# NixieClock_2_1.net
KiCad netlist of a schematic drawn in EAGLE
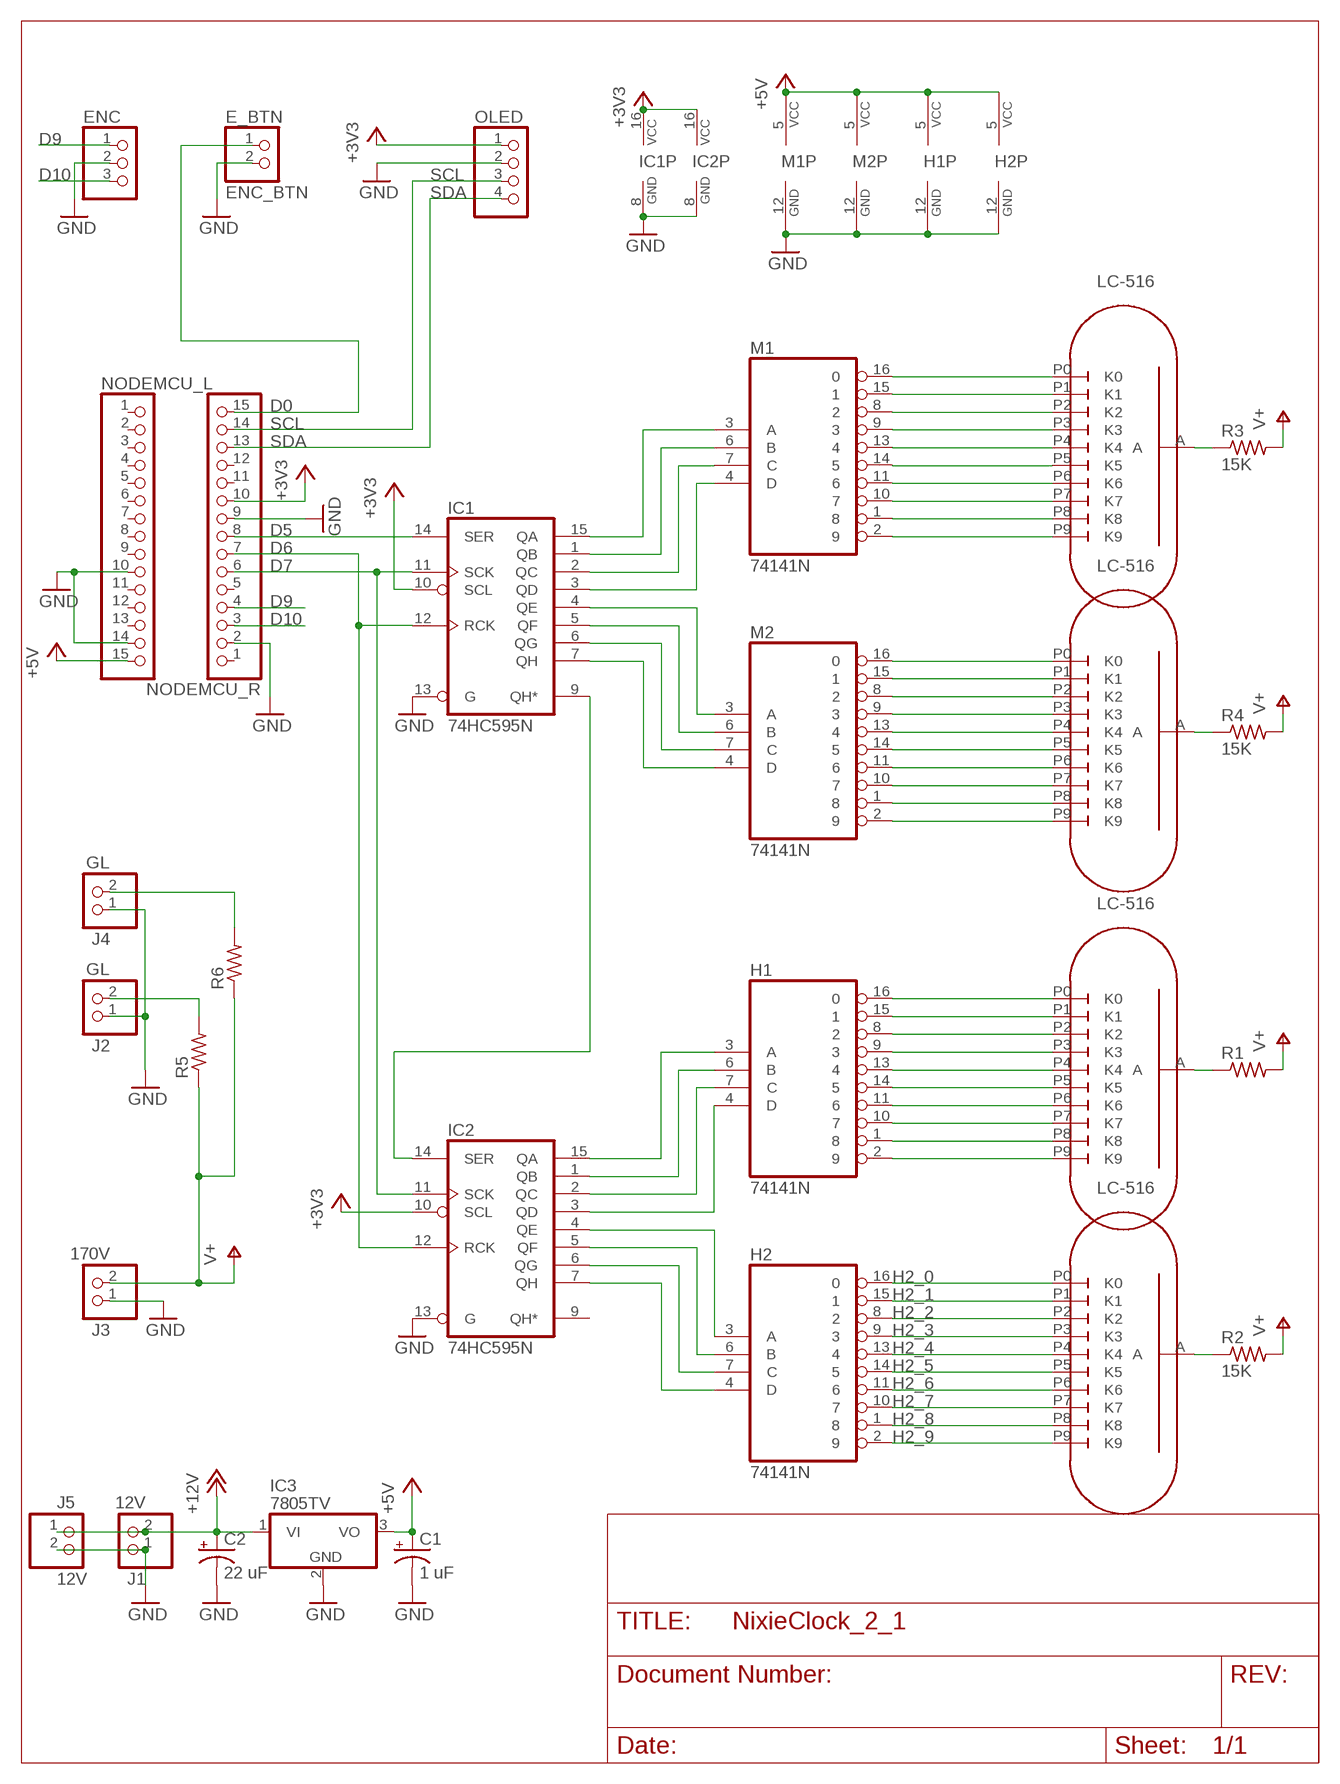
[diagram p0: schematic, sheet 1]

(export (version "E")
  (design (tool "Eeschema 10.0.6"))
  (components
    (comp (ref "C1")
      (value "1 uF")
      (footprint "eagle-import:TT2D5")
      (libsource (lib "eagle-import") (part "CPOL-USTT2D5"))
    )
    (comp (ref "C2")
      (value "22 uF")
      (footprint "eagle-import:TT2D5")
      (libsource (lib "eagle-import") (part "CPOL-USTT2D5"))
    )
    (comp (ref "ENC")
      (value "PINHD-1X3")
      (footprint "eagle-import:1X03")
      (libsource (lib "eagle-import") (part "PINHD-1X3"))
    )
    (comp (ref "E_BTN")
      (value "ENC_BTN")
      (footprint "eagle-import:1X02")
      (libsource (lib "eagle-import") (part "PINHD-1X2"))
    )
    (comp (ref "H1")
      (value "74141N")
      (footprint "eagle-import:DIL16")
      (libsource (lib "eagle-import") (part "74141N"))
    )
    (comp (ref "H2")
      (value "74141N")
      (footprint "eagle-import:DIL16")
      (libsource (lib "eagle-import") (part "74141N"))
    )
    (comp (ref "IC1")
      (value "74HC595N")
      (footprint "eagle-import:DIL16")
      (libsource (lib "eagle-import") (part "74595NHC"))
    )
    (comp (ref "IC2")
      (value "74HC595N")
      (footprint "eagle-import:DIL16")
      (libsource (lib "eagle-import") (part "74595NHC"))
    )
    (comp (ref "IC3")
      (value "7805TV")
      (footprint "eagle-import:TO220V")
      (libsource (lib "eagle-import") (part "78TV05"))
    )
    (comp (ref "J1")
      (value "12V")
      (footprint "eagle-import:1X02")
      (libsource (lib "eagle-import") (part "PINHD-1X2"))
    )
    (comp (ref "J2")
      (value "GL")
      (footprint "eagle-import:1X02")
      (libsource (lib "eagle-import") (part "PINHD-1X2"))
    )
    (comp (ref "J3")
      (value "170V")
      (footprint "eagle-import:1X02")
      (libsource (lib "eagle-import") (part "PINHD-1X2"))
    )
    (comp (ref "J4")
      (value "GL")
      (footprint "eagle-import:1X02")
      (libsource (lib "eagle-import") (part "PINHD-1X2"))
    )
    (comp (ref "J5")
      (value "12V")
      (footprint "eagle-import:1X02")
      (libsource (lib "eagle-import") (part "PINHD-1X2"))
    )
    (comp (ref "M1")
      (value "74141N")
      (footprint "eagle-import:DIL16")
      (libsource (lib "eagle-import") (part "74141N"))
    )
    (comp (ref "M2")
      (value "74141N")
      (footprint "eagle-import:DIL16")
      (libsource (lib "eagle-import") (part "74141N"))
    )
    (comp (ref "NODEMCU_L")
      (value "PINHD-1X15")
      (footprint "eagle-import:1X15")
      (libsource (lib "eagle-import") (part "PINHD-1X15"))
    )
    (comp (ref "NODEMCU_R")
      (value "PINHD-1X15")
      (footprint "eagle-import:1X15")
      (libsource (lib "eagle-import") (part "PINHD-1X15"))
    )
    (comp (ref "OLED")
      (value "PINHD-1X4")
      (footprint "eagle-import:1X04")
      (libsource (lib "eagle-import") (part "PINHD-1X4"))
    )
    (comp (ref "R1")
      (value "15K")
      (footprint "eagle-import:0207_10")
      (libsource (lib "eagle-import") (part "R-US_0207/10"))
    )
    (comp (ref "R2")
      (value "15K")
      (footprint "eagle-import:0207_10")
      (libsource (lib "eagle-import") (part "R-US_0207/10"))
    )
    (comp (ref "R3")
      (value "15K")
      (footprint "eagle-import:0207_10")
      (libsource (lib "eagle-import") (part "R-US_0207/10"))
    )
    (comp (ref "R4")
      (value "15K")
      (footprint "eagle-import:0207_10")
      (libsource (lib "eagle-import") (part "R-US_0207/10"))
    )
    (comp (ref "R5")
      (value "100k")
      (footprint "eagle-import:0207_10")
      (libsource (lib "eagle-import") (part "R-US_0207/10"))
    )
    (comp (ref "R6")
      (value "100k")
      (footprint "eagle-import:0207_10")
      (libsource (lib "eagle-import") (part "R-US_0207/10"))
    )
    (comp (ref "U$1M2")
      (value "LC-516")
      (footprint "eagle-import:LC-516")
      (libsource (lib "eagle-import") (part "LC-516"))
    )
    (comp (ref "U$2M1")
      (value "LC-516")
      (footprint "eagle-import:LC-516")
      (libsource (lib "eagle-import") (part "LC-516"))
    )
    (comp (ref "U$3H2")
      (value "LC-516")
      (footprint "eagle-import:LC-516")
      (libsource (lib "eagle-import") (part "LC-516"))
    )
    (comp (ref "U$4H1")
      (value "LC-516")
      (footprint "eagle-import:LC-516")
      (libsource (lib "eagle-import") (part "LC-516"))
    )
  )
  (nets
    (net (code "1") (name "+3V3") (class "Default")
      (node (ref "IC1") (pin "10") (pinfunction "SCL_10") (pintype "input"))
      (node (ref "IC1") (pin "16") (pinfunction "VCC_16") (pintype "power_in"))
      (node (ref "IC2") (pin "10") (pinfunction "SCL_10") (pintype "input"))
      (node (ref "IC2") (pin "16") (pinfunction "VCC_16") (pintype "power_in"))
      (node (ref "NODEMCU_R") (pin "10") (pinfunction "10_10") (pintype "passive"))
      (node (ref "OLED") (pin "1") (pinfunction "1_1") (pintype "passive"))
    )
    (net (code "2") (name "+5V") (class "Default")
      (node (ref "C1") (pin "+") (pinfunction "+_+") (pintype "passive"))
      (node (ref "H1") (pin "5") (pinfunction "VCC_5") (pintype "power_in"))
      (node (ref "H2") (pin "5") (pinfunction "VCC_5") (pintype "power_in"))
      (node (ref "IC3") (pin "3") (pinfunction "VO_3") (pintype "passive"))
      (node (ref "M1") (pin "5") (pinfunction "VCC_5") (pintype "power_in"))
      (node (ref "M2") (pin "5") (pinfunction "VCC_5") (pintype "power_in"))
      (node (ref "NODEMCU_L") (pin "15") (pinfunction "15_15") (pintype "passive"))
    )
    (net (code "3") (name "+12V") (class "Default")
      (node (ref "C2") (pin "+") (pinfunction "+_+") (pintype "passive"))
      (node (ref "IC3") (pin "1") (pinfunction "VI_1") (pintype "input"))
      (node (ref "J1") (pin "2") (pinfunction "2_2") (pintype "passive"))
      (node (ref "J5") (pin "1") (pinfunction "1_1") (pintype "passive"))
    )
    (net (code "4") (name "/D0") (class "Default")
      (node (ref "E_BTN") (pin "1") (pinfunction "1_1") (pintype "passive"))
      (node (ref "NODEMCU_R") (pin "15") (pinfunction "15_15") (pintype "passive"))
    )
    (net (code "5") (name "/D5") (class "Default")
      (node (ref "IC1") (pin "14") (pinfunction "SER_14") (pintype "input"))
      (node (ref "NODEMCU_R") (pin "8") (pinfunction "8_8") (pintype "passive"))
    )
    (net (code "6") (name "/D6") (class "Default")
      (node (ref "IC1") (pin "12") (pinfunction "RCK_12") (pintype "input"))
      (node (ref "IC2") (pin "12") (pinfunction "RCK_12") (pintype "input"))
      (node (ref "NODEMCU_R") (pin "7") (pinfunction "7_7") (pintype "passive"))
    )
    (net (code "7") (name "/D7") (class "Default")
      (node (ref "IC1") (pin "11") (pinfunction "SCK_11") (pintype "input"))
      (node (ref "IC2") (pin "11") (pinfunction "SCK_11") (pintype "input"))
      (node (ref "NODEMCU_R") (pin "6") (pinfunction "6_6") (pintype "passive"))
    )
    (net (code "8") (name "/D9") (class "Default")
      (node (ref "ENC") (pin "1") (pinfunction "1_1") (pintype "passive"))
      (node (ref "NODEMCU_R") (pin "4") (pinfunction "4_4") (pintype "passive"))
    )
    (net (code "9") (name "/D10") (class "Default")
      (node (ref "ENC") (pin "3") (pinfunction "3_3") (pintype "passive"))
      (node (ref "NODEMCU_R") (pin "3") (pinfunction "3_3") (pintype "passive"))
    )
    (net (code "10") (name "/H2_0") (class "Default")
      (node (ref "H2") (pin "16") (pinfunction "0_16") (pintype "open_collector"))
      (node (ref "U$4H1") (pin "P0") (pinfunction "K0_P0") (pintype "bidirectional"))
    )
    (net (code "11") (name "/H2_1") (class "Default")
      (node (ref "H2") (pin "15") (pinfunction "1_15") (pintype "open_collector"))
      (node (ref "U$4H1") (pin "P1") (pinfunction "K1_P1") (pintype "bidirectional"))
    )
    (net (code "12") (name "/H2_2") (class "Default")
      (node (ref "H2") (pin "8") (pinfunction "2_8") (pintype "open_collector"))
      (node (ref "U$4H1") (pin "P2") (pinfunction "K2_P2") (pintype "bidirectional"))
    )
    (net (code "13") (name "/H2_3") (class "Default")
      (node (ref "H2") (pin "9") (pinfunction "3_9") (pintype "open_collector"))
      (node (ref "U$4H1") (pin "P3") (pinfunction "K3_P3") (pintype "bidirectional"))
    )
    (net (code "14") (name "/H2_4") (class "Default")
      (node (ref "H2") (pin "13") (pinfunction "4_13") (pintype "open_collector"))
      (node (ref "U$4H1") (pin "P4") (pinfunction "K4_P4") (pintype "bidirectional"))
    )
    (net (code "15") (name "/H2_5") (class "Default")
      (node (ref "H2") (pin "14") (pinfunction "5_14") (pintype "open_collector"))
      (node (ref "U$4H1") (pin "P5") (pinfunction "K5_P5") (pintype "bidirectional"))
    )
    (net (code "16") (name "/H2_6") (class "Default")
      (node (ref "H2") (pin "11") (pinfunction "6_11") (pintype "open_collector"))
      (node (ref "U$4H1") (pin "P6") (pinfunction "K6_P6") (pintype "bidirectional"))
    )
    (net (code "17") (name "/H2_7") (class "Default")
      (node (ref "H2") (pin "10") (pinfunction "7_10") (pintype "open_collector"))
      (node (ref "U$4H1") (pin "P7") (pinfunction "K7_P7") (pintype "bidirectional"))
    )
    (net (code "18") (name "/H2_8") (class "Default")
      (node (ref "H2") (pin "1") (pinfunction "8_1") (pintype "open_collector"))
      (node (ref "U$4H1") (pin "P8") (pinfunction "K8_P8") (pintype "bidirectional"))
    )
    (net (code "19") (name "/H2_9") (class "Default")
      (node (ref "H2") (pin "2") (pinfunction "9_2") (pintype "open_collector"))
      (node (ref "U$4H1") (pin "P9") (pinfunction "K9_P9") (pintype "bidirectional"))
    )
    (net (code "20") (name "/SCL") (class "Default")
      (node (ref "NODEMCU_R") (pin "14") (pinfunction "14_14") (pintype "passive"))
      (node (ref "OLED") (pin "3") (pinfunction "3_3") (pintype "passive"))
    )
    (net (code "21") (name "/SDA") (class "Default")
      (node (ref "NODEMCU_R") (pin "13") (pinfunction "13_13") (pintype "passive"))
      (node (ref "OLED") (pin "4") (pinfunction "4_4") (pintype "passive"))
    )
    (net (code "22") (name "GND") (class "Default")
      (node (ref "C1") (pin "-") (pinfunction "-_-") (pintype "passive"))
      (node (ref "C2") (pin "-") (pinfunction "-_-") (pintype "passive"))
      (node (ref "ENC") (pin "2") (pinfunction "2_2") (pintype "passive"))
      (node (ref "E_BTN") (pin "2") (pinfunction "2_2") (pintype "passive"))
      (node (ref "H1") (pin "12") (pinfunction "GND_12") (pintype "power_in"))
      (node (ref "H2") (pin "12") (pinfunction "GND_12") (pintype "power_in"))
      (node (ref "IC1") (pin "13") (pinfunction "G_13") (pintype "input"))
      (node (ref "IC1") (pin "8") (pinfunction "GND_8") (pintype "power_in"))
      (node (ref "IC2") (pin "13") (pinfunction "G_13") (pintype "input"))
      (node (ref "IC2") (pin "8") (pinfunction "GND_8") (pintype "power_in"))
      (node (ref "IC3") (pin "2") (pinfunction "GND_2") (pintype "passive"))
      (node (ref "J1") (pin "1") (pinfunction "1_1") (pintype "passive"))
      (node (ref "J2") (pin "1") (pinfunction "1_1") (pintype "passive"))
      (node (ref "J3") (pin "1") (pinfunction "1_1") (pintype "passive"))
      (node (ref "J4") (pin "1") (pinfunction "1_1") (pintype "passive"))
      (node (ref "J5") (pin "2") (pinfunction "2_2") (pintype "passive"))
      (node (ref "M1") (pin "12") (pinfunction "GND_12") (pintype "power_in"))
      (node (ref "M2") (pin "12") (pinfunction "GND_12") (pintype "power_in"))
      (node (ref "NODEMCU_L") (pin "10") (pinfunction "10_10") (pintype "passive"))
      (node (ref "NODEMCU_L") (pin "14") (pinfunction "14_14") (pintype "passive"))
      (node (ref "NODEMCU_R") (pin "2") (pinfunction "2_2") (pintype "passive"))
      (node (ref "NODEMCU_R") (pin "9") (pinfunction "9_9") (pintype "passive"))
      (node (ref "OLED") (pin "2") (pinfunction "2_2") (pintype "passive"))
    )
    (net (code "23") (name "Net-(H1A-0)") (class "Default")
      (node (ref "H1") (pin "16") (pinfunction "0_16") (pintype "open_collector"))
      (node (ref "U$3H2") (pin "P0") (pinfunction "K0_P0") (pintype "bidirectional"))
    )
    (net (code "24") (name "Net-(H1A-1)") (class "Default")
      (node (ref "H1") (pin "15") (pinfunction "1_15") (pintype "open_collector"))
      (node (ref "U$3H2") (pin "P1") (pinfunction "K1_P1") (pintype "bidirectional"))
    )
    (net (code "25") (name "Net-(H1A-2)") (class "Default")
      (node (ref "H1") (pin "8") (pinfunction "2_8") (pintype "open_collector"))
      (node (ref "U$3H2") (pin "P2") (pinfunction "K2_P2") (pintype "bidirectional"))
    )
    (net (code "26") (name "Net-(H1A-3)") (class "Default")
      (node (ref "H1") (pin "9") (pinfunction "3_9") (pintype "open_collector"))
      (node (ref "U$3H2") (pin "P3") (pinfunction "K3_P3") (pintype "bidirectional"))
    )
    (net (code "27") (name "Net-(H1A-4)") (class "Default")
      (node (ref "H1") (pin "13") (pinfunction "4_13") (pintype "open_collector"))
      (node (ref "U$3H2") (pin "P4") (pinfunction "K4_P4") (pintype "bidirectional"))
    )
    (net (code "28") (name "Net-(H1A-5)") (class "Default")
      (node (ref "H1") (pin "14") (pinfunction "5_14") (pintype "open_collector"))
      (node (ref "U$3H2") (pin "P5") (pinfunction "K5_P5") (pintype "bidirectional"))
    )
    (net (code "29") (name "Net-(H1A-6)") (class "Default")
      (node (ref "H1") (pin "11") (pinfunction "6_11") (pintype "open_collector"))
      (node (ref "U$3H2") (pin "P6") (pinfunction "K6_P6") (pintype "bidirectional"))
    )
    (net (code "30") (name "Net-(H1A-7)") (class "Default")
      (node (ref "H1") (pin "10") (pinfunction "7_10") (pintype "open_collector"))
      (node (ref "U$3H2") (pin "P7") (pinfunction "K7_P7") (pintype "bidirectional"))
    )
    (net (code "31") (name "Net-(H1A-8)") (class "Default")
      (node (ref "H1") (pin "1") (pinfunction "8_1") (pintype "open_collector"))
      (node (ref "U$3H2") (pin "P8") (pinfunction "K8_P8") (pintype "bidirectional"))
    )
    (net (code "32") (name "Net-(H1A-9)") (class "Default")
      (node (ref "H1") (pin "2") (pinfunction "9_2") (pintype "open_collector"))
      (node (ref "U$3H2") (pin "P9") (pinfunction "K9_P9") (pintype "bidirectional"))
    )
    (net (code "33") (name "Net-(H1A-A)") (class "Default")
      (node (ref "H1") (pin "3") (pinfunction "A_3") (pintype "input"))
      (node (ref "IC2") (pin "15") (pinfunction "QA_15") (pintype "tri_state"))
    )
    (net (code "34") (name "Net-(H1A-B)") (class "Default")
      (node (ref "H1") (pin "6") (pinfunction "B_6") (pintype "input"))
      (node (ref "IC2") (pin "1") (pinfunction "QB_1") (pintype "tri_state"))
    )
    (net (code "35") (name "Net-(H1A-C)") (class "Default")
      (node (ref "H1") (pin "7") (pinfunction "C_7") (pintype "input"))
      (node (ref "IC2") (pin "2") (pinfunction "QC_2") (pintype "tri_state"))
    )
    (net (code "36") (name "Net-(H1A-D)") (class "Default")
      (node (ref "H1") (pin "4") (pinfunction "D_4") (pintype "input"))
      (node (ref "IC2") (pin "3") (pinfunction "QD_3") (pintype "tri_state"))
    )
    (net (code "37") (name "Net-(H2A-A)") (class "Default")
      (node (ref "H2") (pin "3") (pinfunction "A_3") (pintype "input"))
      (node (ref "IC2") (pin "4") (pinfunction "QE_4") (pintype "tri_state"))
    )
    (net (code "38") (name "Net-(H2A-B)") (class "Default")
      (node (ref "H2") (pin "6") (pinfunction "B_6") (pintype "input"))
      (node (ref "IC2") (pin "5") (pinfunction "QF_5") (pintype "tri_state"))
    )
    (net (code "39") (name "Net-(H2A-C)") (class "Default")
      (node (ref "H2") (pin "7") (pinfunction "C_7") (pintype "input"))
      (node (ref "IC2") (pin "6") (pinfunction "QG_6") (pintype "tri_state"))
    )
    (net (code "40") (name "Net-(H2A-D)") (class "Default")
      (node (ref "H2") (pin "4") (pinfunction "D_4") (pintype "input"))
      (node (ref "IC2") (pin "7") (pinfunction "QH_7") (pintype "tri_state"))
    )
    (net (code "41") (name "Net-(IC1A-QA)") (class "Default")
      (node (ref "IC1") (pin "15") (pinfunction "QA_15") (pintype "tri_state"))
      (node (ref "M1") (pin "3") (pinfunction "A_3") (pintype "input"))
    )
    (net (code "42") (name "Net-(IC1A-QB)") (class "Default")
      (node (ref "IC1") (pin "1") (pinfunction "QB_1") (pintype "tri_state"))
      (node (ref "M1") (pin "6") (pinfunction "B_6") (pintype "input"))
    )
    (net (code "43") (name "Net-(IC1A-QC)") (class "Default")
      (node (ref "IC1") (pin "2") (pinfunction "QC_2") (pintype "tri_state"))
      (node (ref "M1") (pin "7") (pinfunction "C_7") (pintype "input"))
    )
    (net (code "44") (name "Net-(IC1A-QD)") (class "Default")
      (node (ref "IC1") (pin "3") (pinfunction "QD_3") (pintype "tri_state"))
      (node (ref "M1") (pin "4") (pinfunction "D_4") (pintype "input"))
    )
    (net (code "45") (name "Net-(IC1A-QE)") (class "Default")
      (node (ref "IC1") (pin "4") (pinfunction "QE_4") (pintype "tri_state"))
      (node (ref "M2") (pin "3") (pinfunction "A_3") (pintype "input"))
    )
    (net (code "46") (name "Net-(IC1A-QF)") (class "Default")
      (node (ref "IC1") (pin "5") (pinfunction "QF_5") (pintype "tri_state"))
      (node (ref "M2") (pin "6") (pinfunction "B_6") (pintype "input"))
    )
    (net (code "47") (name "Net-(IC1A-QG)") (class "Default")
      (node (ref "IC1") (pin "6") (pinfunction "QG_6") (pintype "tri_state"))
      (node (ref "M2") (pin "7") (pinfunction "C_7") (pintype "input"))
    )
    (net (code "48") (name "Net-(IC1A-QH)") (class "Default")
      (node (ref "IC1") (pin "7") (pinfunction "QH_7") (pintype "tri_state"))
      (node (ref "M2") (pin "4") (pinfunction "D_4") (pintype "input"))
    )
    (net (code "49") (name "Net-(IC1A-QH*)") (class "Default")
      (node (ref "IC1") (pin "9") (pinfunction "QH*_9") (pintype "tri_state"))
      (node (ref "IC2") (pin "14") (pinfunction "SER_14") (pintype "input"))
    )
    (net (code "50") (name "Net-(J2-Pad2)") (class "Default")
      (node (ref "J2") (pin "2") (pinfunction "2_2") (pintype "passive"))
      (node (ref "R5") (pin "2") (pinfunction "2_2") (pintype "passive"))
    )
    (net (code "51") (name "Net-(J4-Pad2)") (class "Default")
      (node (ref "J4") (pin "2") (pinfunction "2_2") (pintype "passive"))
      (node (ref "R6") (pin "2") (pinfunction "2_2") (pintype "passive"))
    )
    (net (code "52") (name "Net-(M1A-0)") (class "Default")
      (node (ref "M1") (pin "16") (pinfunction "0_16") (pintype "open_collector"))
      (node (ref "U$1M2") (pin "P0") (pinfunction "K0_P0") (pintype "bidirectional"))
    )
    (net (code "53") (name "Net-(M1A-1)") (class "Default")
      (node (ref "M1") (pin "15") (pinfunction "1_15") (pintype "open_collector"))
      (node (ref "U$1M2") (pin "P1") (pinfunction "K1_P1") (pintype "bidirectional"))
    )
    (net (code "54") (name "Net-(M1A-2)") (class "Default")
      (node (ref "M1") (pin "8") (pinfunction "2_8") (pintype "open_collector"))
      (node (ref "U$1M2") (pin "P2") (pinfunction "K2_P2") (pintype "bidirectional"))
    )
    (net (code "55") (name "Net-(M1A-3)") (class "Default")
      (node (ref "M1") (pin "9") (pinfunction "3_9") (pintype "open_collector"))
      (node (ref "U$1M2") (pin "P3") (pinfunction "K3_P3") (pintype "bidirectional"))
    )
    (net (code "56") (name "Net-(M1A-4)") (class "Default")
      (node (ref "M1") (pin "13") (pinfunction "4_13") (pintype "open_collector"))
      (node (ref "U$1M2") (pin "P4") (pinfunction "K4_P4") (pintype "bidirectional"))
    )
    (net (code "57") (name "Net-(M1A-5)") (class "Default")
      (node (ref "M1") (pin "14") (pinfunction "5_14") (pintype "open_collector"))
      (node (ref "U$1M2") (pin "P5") (pinfunction "K5_P5") (pintype "bidirectional"))
    )
    (net (code "58") (name "Net-(M1A-6)") (class "Default")
      (node (ref "M1") (pin "11") (pinfunction "6_11") (pintype "open_collector"))
      (node (ref "U$1M2") (pin "P6") (pinfunction "K6_P6") (pintype "bidirectional"))
    )
    (net (code "59") (name "Net-(M1A-7)") (class "Default")
      (node (ref "M1") (pin "10") (pinfunction "7_10") (pintype "open_collector"))
      (node (ref "U$1M2") (pin "P7") (pinfunction "K7_P7") (pintype "bidirectional"))
    )
    (net (code "60") (name "Net-(M1A-8)") (class "Default")
      (node (ref "M1") (pin "1") (pinfunction "8_1") (pintype "open_collector"))
      (node (ref "U$1M2") (pin "P8") (pinfunction "K8_P8") (pintype "bidirectional"))
    )
    (net (code "61") (name "Net-(M1A-9)") (class "Default")
      (node (ref "M1") (pin "2") (pinfunction "9_2") (pintype "open_collector"))
      (node (ref "U$1M2") (pin "P9") (pinfunction "K9_P9") (pintype "bidirectional"))
    )
    (net (code "62") (name "Net-(M2A-0)") (class "Default")
      (node (ref "M2") (pin "16") (pinfunction "0_16") (pintype "open_collector"))
      (node (ref "U$2M1") (pin "P0") (pinfunction "K0_P0") (pintype "bidirectional"))
    )
    (net (code "63") (name "Net-(M2A-1)") (class "Default")
      (node (ref "M2") (pin "15") (pinfunction "1_15") (pintype "open_collector"))
      (node (ref "U$2M1") (pin "P1") (pinfunction "K1_P1") (pintype "bidirectional"))
    )
    (net (code "64") (name "Net-(M2A-2)") (class "Default")
      (node (ref "M2") (pin "8") (pinfunction "2_8") (pintype "open_collector"))
      (node (ref "U$2M1") (pin "P2") (pinfunction "K2_P2") (pintype "bidirectional"))
    )
    (net (code "65") (name "Net-(M2A-3)") (class "Default")
      (node (ref "M2") (pin "9") (pinfunction "3_9") (pintype "open_collector"))
      (node (ref "U$2M1") (pin "P3") (pinfunction "K3_P3") (pintype "bidirectional"))
    )
    (net (code "66") (name "Net-(M2A-4)") (class "Default")
      (node (ref "M2") (pin "13") (pinfunction "4_13") (pintype "open_collector"))
      (node (ref "U$2M1") (pin "P4") (pinfunction "K4_P4") (pintype "bidirectional"))
    )
    (net (code "67") (name "Net-(M2A-5)") (class "Default")
      (node (ref "M2") (pin "14") (pinfunction "5_14") (pintype "open_collector"))
      (node (ref "U$2M1") (pin "P5") (pinfunction "K5_P5") (pintype "bidirectional"))
    )
    (net (code "68") (name "Net-(M2A-6)") (class "Default")
      (node (ref "M2") (pin "11") (pinfunction "6_11") (pintype "open_collector"))
      (node (ref "U$2M1") (pin "P6") (pinfunction "K6_P6") (pintype "bidirectional"))
    )
    (net (code "69") (name "Net-(M2A-7)") (class "Default")
      (node (ref "M2") (pin "10") (pinfunction "7_10") (pintype "open_collector"))
      (node (ref "U$2M1") (pin "P7") (pinfunction "K7_P7") (pintype "bidirectional"))
    )
    (net (code "70") (name "Net-(M2A-8)") (class "Default")
      (node (ref "M2") (pin "1") (pinfunction "8_1") (pintype "open_collector"))
      (node (ref "U$2M1") (pin "P8") (pinfunction "K8_P8") (pintype "bidirectional"))
    )
    (net (code "71") (name "Net-(M2A-9)") (class "Default")
      (node (ref "M2") (pin "2") (pinfunction "9_2") (pintype "open_collector"))
      (node (ref "U$2M1") (pin "P9") (pinfunction "K9_P9") (pintype "bidirectional"))
    )
    (net (code "72") (name "Net-(R1-Pad1)") (class "Default")
      (node (ref "R1") (pin "1") (pinfunction "1_1") (pintype "passive"))
      (node (ref "U$3H2") (pin "A") (pinfunction "A_A") (pintype "bidirectional"))
    )
    (net (code "73") (name "Net-(R2-Pad1)") (class "Default")
      (node (ref "R2") (pin "1") (pinfunction "1_1") (pintype "passive"))
      (node (ref "U$4H1") (pin "A") (pinfunction "A_A") (pintype "bidirectional"))
    )
    (net (code "74") (name "Net-(R3-Pad1)") (class "Default")
      (node (ref "R3") (pin "1") (pinfunction "1_1") (pintype "passive"))
      (node (ref "U$1M2") (pin "A") (pinfunction "A_A") (pintype "bidirectional"))
    )
    (net (code "75") (name "Net-(R4-Pad1)") (class "Default")
      (node (ref "R4") (pin "1") (pinfunction "1_1") (pintype "passive"))
      (node (ref "U$2M1") (pin "A") (pinfunction "A_A") (pintype "bidirectional"))
    )
    (net (code "76") (name "V+") (class "Default")
      (node (ref "J3") (pin "2") (pinfunction "2_2") (pintype "passive"))
      (node (ref "R1") (pin "2") (pinfunction "2_2") (pintype "passive"))
      (node (ref "R2") (pin "2") (pinfunction "2_2") (pintype "passive"))
      (node (ref "R3") (pin "2") (pinfunction "2_2") (pintype "passive"))
      (node (ref "R4") (pin "2") (pinfunction "2_2") (pintype "passive"))
      (node (ref "R5") (pin "1") (pinfunction "1_1") (pintype "passive"))
      (node (ref "R6") (pin "1") (pinfunction "1_1") (pintype "passive"))
    )
    (net (code "77") (name "unconnected-(IC2A-QH*-Pad9)") (class "Default")
      (node (ref "IC2") (pin "9") (pinfunction "QH*_9") (pintype "tri_state"))
    )
    (net (code "78") (name "unconnected-(NODEMCU_L-Pad1)") (class "Default")
      (node (ref "NODEMCU_L") (pin "1") (pinfunction "1_1") (pintype "passive"))
    )
    (net (code "79") (name "unconnected-(NODEMCU_L-Pad2)") (class "Default")
      (node (ref "NODEMCU_L") (pin "2") (pinfunction "2_2") (pintype "passive"))
    )
    (net (code "80") (name "unconnected-(NODEMCU_L-Pad3)") (class "Default")
      (node (ref "NODEMCU_L") (pin "3") (pinfunction "3_3") (pintype "passive"))
    )
    (net (code "81") (name "unconnected-(NODEMCU_L-Pad4)") (class "Default")
      (node (ref "NODEMCU_L") (pin "4") (pinfunction "4_4") (pintype "passive"))
    )
    (net (code "82") (name "unconnected-(NODEMCU_L-Pad5)") (class "Default")
      (node (ref "NODEMCU_L") (pin "5") (pinfunction "5_5") (pintype "passive"))
    )
    (net (code "83") (name "unconnected-(NODEMCU_L-Pad6)") (class "Default")
      (node (ref "NODEMCU_L") (pin "6") (pinfunction "6_6") (pintype "passive"))
    )
    (net (code "84") (name "unconnected-(NODEMCU_L-Pad7)") (class "Default")
      (node (ref "NODEMCU_L") (pin "7") (pinfunction "7_7") (pintype "passive"))
    )
    (net (code "85") (name "unconnected-(NODEMCU_L-Pad8)") (class "Default")
      (node (ref "NODEMCU_L") (pin "8") (pinfunction "8_8") (pintype "passive"))
    )
    (net (code "86") (name "unconnected-(NODEMCU_L-Pad9)") (class "Default")
      (node (ref "NODEMCU_L") (pin "9") (pinfunction "9_9") (pintype "passive"))
    )
    (net (code "87") (name "unconnected-(NODEMCU_L-Pad11)") (class "Default")
      (node (ref "NODEMCU_L") (pin "11") (pinfunction "11_11") (pintype "passive"))
    )
    (net (code "88") (name "unconnected-(NODEMCU_L-Pad12)") (class "Default")
      (node (ref "NODEMCU_L") (pin "12") (pinfunction "12_12") (pintype "passive"))
    )
    (net (code "89") (name "unconnected-(NODEMCU_L-Pad13)") (class "Default")
      (node (ref "NODEMCU_L") (pin "13") (pinfunction "13_13") (pintype "passive"))
    )
    (net (code "90") (name "unconnected-(NODEMCU_R-Pad1)") (class "Default")
      (node (ref "NODEMCU_R") (pin "1") (pinfunction "1_1") (pintype "passive"))
    )
    (net (code "91") (name "unconnected-(NODEMCU_R-Pad5)") (class "Default")
      (node (ref "NODEMCU_R") (pin "5") (pinfunction "5_5") (pintype "passive"))
    )
    (net (code "92") (name "unconnected-(NODEMCU_R-Pad11)") (class "Default")
      (node (ref "NODEMCU_R") (pin "11") (pinfunction "11_11") (pintype "passive"))
    )
    (net (code "93") (name "unconnected-(NODEMCU_R-Pad12)") (class "Default")
      (node (ref "NODEMCU_R") (pin "12") (pinfunction "12_12") (pintype "passive"))
    )
  )
)
